# Fri3D_2020_GameOn_00.net
KiCad netlist of a schematic drawn in Altium Designer
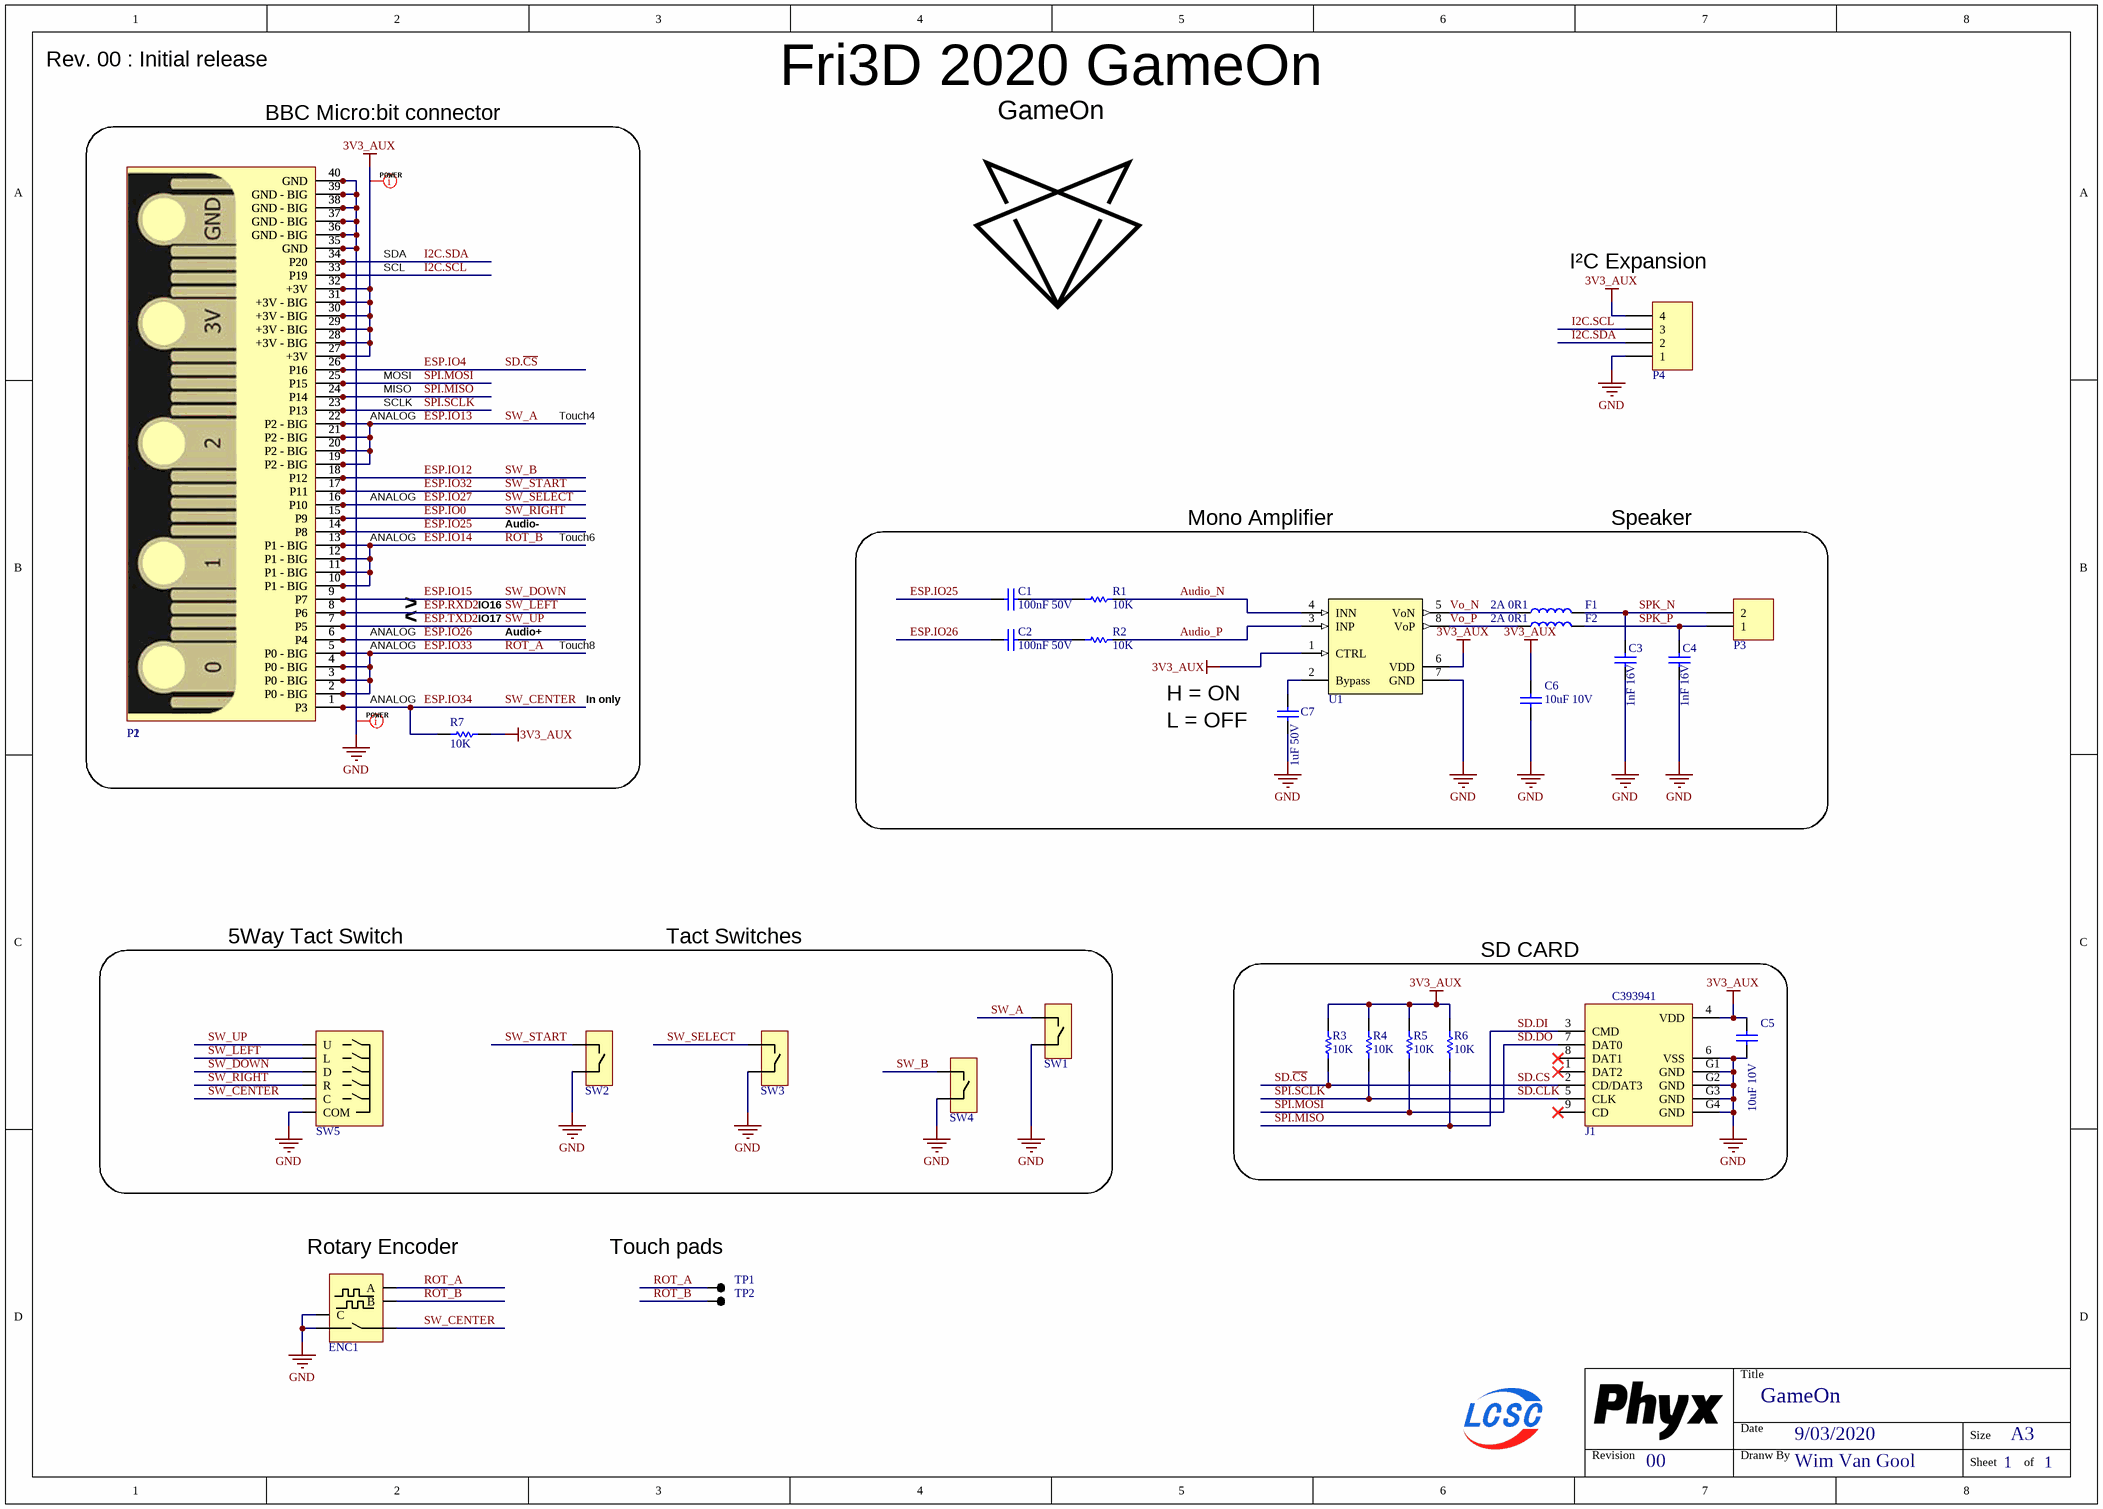
[diagram p0: Fri3D_2020_GameOn_00.SchDoc]

(export (version "E")
  (design (tool "Eeschema 10.0.6"))
  (components
    (comp (ref "C1")
      (value "100nF 50V")
      (footprint "C0603_N")
      (description "Capacitor Ceramic")
      (fields (field (name "Comment") "CAP_CERAMIC"))
      (libsource (lib "Phyx_Components") (part "CAP_CERAMIC"))
    )
    (comp (ref "C2")
      (value "100nF 50V")
      (footprint "C0603_N")
      (description "Capacitor Ceramic")
      (fields (field (name "Comment") "CAP_CERAMIC"))
      (libsource (lib "Phyx_Components") (part "CAP_CERAMIC"))
    )
    (comp (ref "C3")
      (value "1nF 16V")
      (footprint "C0603_N")
      (description "Capacitor Ceramic")
      (fields (field (name "Comment") "CAP_CERAMIC"))
      (libsource (lib "Phyx_Components") (part "CAP_CERAMIC"))
    )
    (comp (ref "C4")
      (value "1nF 16V")
      (footprint "C0603_N")
      (description "Capacitor Ceramic")
      (fields (field (name "Comment") "CAP_CERAMIC"))
      (libsource (lib "Phyx_Components") (part "CAP_CERAMIC"))
    )
    (comp (ref "C5")
      (value "10uF 10V")
      (footprint "C0805_N")
      (description "Capacitor Ceramic")
      (fields (field (name "Comment") "CAP_CERAMIC"))
      (libsource (lib "Phyx_Components") (part "CAP_CERAMIC"))
    )
    (comp (ref "C6")
      (value "10uF 10V")
      (footprint "C0805_N")
      (description "Capacitor Ceramic")
      (fields (field (name "Comment") "CAP_CERAMIC"))
      (libsource (lib "Phyx_Components") (part "CAP_CERAMIC"))
    )
    (comp (ref "C7")
      (value "1uF 50V")
      (footprint "C0603_N")
      (description "Capacitor Ceramic")
      (fields (field (name "Comment") "CAP_CERAMIC"))
      (libsource (lib "Phyx_Components") (part "CAP_CERAMIC"))
    )
    (comp (ref "ENC1")
      (value "Rotary Encoder with Switch")
      (footprint "PEC11-4215F-S0024")
      (libsource (lib "Phyx_Components") (part "ROT_ENC_3P_SW"))
    )
    (comp (ref "F1")
      (value "2A 0R1")
      (footprint "L0805")
      (fields (field (name "Comment") "FERRITE"))
      (libsource (lib "Phyx_Components") (part "FERRITE"))
    )
    (comp (ref "F2")
      (value "2A 0R1")
      (footprint "L0805")
      (fields (field (name "Comment") "FERRITE"))
      (libsource (lib "Phyx_Components") (part "FERRITE"))
    )
    (comp (ref "J1")
      (value "Micro SD PiPo Push-Push")
      (footprint "TFP09-2-12B")
      (description "=Description")
      (fields (field (name "SUPPLIER PART NUMBER 1") "C393941"))
      (libsource (lib "Phyx_Components") (part "TFP09-2-12B"))
    )
    (comp (ref "P1")
      (value "MicroBit 90deg connector Cylconn")
      (footprint "MicroBIT_CYLCONN_SMD_90")
      (libsource (lib "Phyx_Components") (part "Header 40_MicroBit"))
    )
    (comp (ref "P2")
      (value "MicroBit 180deg connector Cylconn")
      (footprint "MicroBIT_CYLCONN_SMD_180")
      (libsource (lib "Phyx_Components") (part "Header 40_MicroBit"))
    )
    (comp (ref "P3")
      (value "Header 2")
      (footprint "HDR1X2")
      (libsource (lib "Phyx_Components") (part "Header 2"))
    )
    (comp (ref "P4")
      (value "Header 4")
      (footprint "HDR1X4")
      (libsource (lib "Phyx_Components") (part "Header 4"))
    )
    (comp (ref "R1")
      (value "10K")
      (footprint "R0603_N")
      (fields (field (name "Comment") "RESISTOR"))
      (libsource (lib "Phyx_Components") (part "RESISTOR"))
    )
    (comp (ref "R2")
      (value "10K")
      (footprint "R0603_N")
      (fields (field (name "Comment") "RESISTOR"))
      (libsource (lib "Phyx_Components") (part "RESISTOR"))
    )
    (comp (ref "R3")
      (value "10K")
      (footprint "R0603_N")
      (fields (field (name "Comment") "RESISTOR"))
      (libsource (lib "Phyx_Components") (part "RESISTOR"))
    )
    (comp (ref "R4")
      (value "10K")
      (footprint "R0603_N")
      (fields (field (name "Comment") "RESISTOR"))
      (libsource (lib "Phyx_Components") (part "RESISTOR"))
    )
    (comp (ref "R5")
      (value "10K")
      (footprint "R0603_N")
      (fields (field (name "Comment") "RESISTOR"))
      (libsource (lib "Phyx_Components") (part "RESISTOR"))
    )
    (comp (ref "R6")
      (value "10K")
      (footprint "R0603_N")
      (fields (field (name "Comment") "RESISTOR"))
      (libsource (lib "Phyx_Components") (part "RESISTOR"))
    )
    (comp (ref "R7")
      (value "10K")
      (footprint "R0603_N")
      (fields (field (name "Comment") "RESISTOR"))
      (libsource (lib "Phyx_Components") (part "RESISTOR"))
    )
    (comp (ref "SW1")
      (value "Default TH TACT")
      (footprint "TACTSW")
      (libsource (lib "Phyx_Components") (part "SW_TACT"))
    )
    (comp (ref "SW2")
      (value "Default TH TACT")
      (footprint "TACTSW")
      (libsource (lib "Phyx_Components") (part "SW_TACT"))
    )
    (comp (ref "SW3")
      (value "Default TH TACT")
      (footprint "TACTSW")
      (libsource (lib "Phyx_Components") (part "SW_TACT"))
    )
    (comp (ref "SW4")
      (value "Default TH TACT")
      (footprint "TACTSW")
      (libsource (lib "Phyx_Components") (part "SW_TACT"))
    )
    (comp (ref "SW5")
      (value "5Way Tact switch")
      (footprint "TACTSW_5W_K1-1506DN-01")
      (libsource (lib "Phyx_Components") (part "SW_TACT_5WAY"))
    )
    (comp (ref "TP1")
      (value "TEST_PAD")
      (footprint "TP_1.2mm")
      (libsource (lib "Phyx_Components") (part "TEST_PAD"))
    )
    (comp (ref "TP2")
      (value "TEST_PAD")
      (footprint "TP_1.2mm")
      (libsource (lib "Phyx_Components") (part "TEST_PAD"))
    )
    (comp (ref "U1")
      (value "5W Class D mono amplifier inducter-less Differential input MSOP8")
      (footprint "MAX_uSOP8")
      (description "=Description")
      (libsource (lib "Phyx_Components") (part "NS4150"))
    )
  )
  (nets
    (net (code "1") (name "/Audio_N") (class "Default")
      (node (ref "R1") (pin "2") (pinfunction "2_2") (pintype "passive"))
      (node (ref "U1") (pin "4") (pinfunction "INN_4") (pintype "input"))
    )
    (net (code "2") (name "/Audio_P") (class "Default")
      (node (ref "R2") (pin "2") (pinfunction "2_2") (pintype "passive"))
      (node (ref "U1") (pin "3") (pinfunction "INP_3") (pintype "input"))
    )
    (net (code "3") (name "/ESP.IO0") (class "Default")
      (node (ref "P1") (pin "15") (pinfunction "P9_15") (pintype "passive"))
      (node (ref "P2") (pin "15") (pinfunction "P9_15") (pintype "passive"))
      (node (ref "SW5") (pin "5") (pinfunction "R_5") (pintype "passive"))
    )
    (net (code "4") (name "/ESP.IO4") (class "Default")
      (node (ref "J1") (pin "2") (pinfunction "CD/DAT3_2") (pintype "passive"))
      (node (ref "P1") (pin "26") (pinfunction "P16_26") (pintype "passive"))
      (node (ref "P2") (pin "26") (pinfunction "P16_26") (pintype "passive"))
      (node (ref "R3") (pin "2") (pinfunction "2_2") (pintype "passive"))
    )
    (net (code "5") (name "/ESP.IO12") (class "Default")
      (node (ref "P1") (pin "18") (pinfunction "P12_18") (pintype "passive"))
      (node (ref "P2") (pin "18") (pinfunction "P12_18") (pintype "passive"))
      (node (ref "SW4") (pin "1") (pinfunction "1_1") (pintype "passive"))
    )
    (net (code "6") (name "/ESP.IO13") (class "Default")
      (node (ref "P1") (pin "19") (pinfunction "P2_-_BIG_19") (pintype "passive"))
      (node (ref "P1") (pin "20") (pinfunction "P2_-_BIG_20") (pintype "passive"))
      (node (ref "P1") (pin "21") (pinfunction "P2_-_BIG_21") (pintype "passive"))
      (node (ref "P1") (pin "22") (pinfunction "P2_-_BIG_22") (pintype "passive"))
      (node (ref "P2") (pin "19") (pinfunction "P2_-_BIG_19") (pintype "passive"))
      (node (ref "P2") (pin "20") (pinfunction "P2_-_BIG_20") (pintype "passive"))
      (node (ref "P2") (pin "21") (pinfunction "P2_-_BIG_21") (pintype "passive"))
      (node (ref "P2") (pin "22") (pinfunction "P2_-_BIG_22") (pintype "passive"))
      (node (ref "SW1") (pin "1") (pinfunction "1_1") (pintype "passive"))
    )
    (net (code "7") (name "/ESP.IO14") (class "Default")
      (node (ref "ENC1") (pin "B") (pinfunction "B_B") (pintype "passive"))
      (node (ref "P1") (pin "10") (pinfunction "P1_-_BIG_10") (pintype "passive"))
      (node (ref "P1") (pin "11") (pinfunction "P1_-_BIG_11") (pintype "passive"))
      (node (ref "P1") (pin "12") (pinfunction "P1_-_BIG_12") (pintype "passive"))
      (node (ref "P1") (pin "13") (pinfunction "P1_-_BIG_13") (pintype "passive"))
      (node (ref "P2") (pin "10") (pinfunction "P1_-_BIG_10") (pintype "passive"))
      (node (ref "P2") (pin "11") (pinfunction "P1_-_BIG_11") (pintype "passive"))
      (node (ref "P2") (pin "12") (pinfunction "P1_-_BIG_12") (pintype "passive"))
      (node (ref "P2") (pin "13") (pinfunction "P1_-_BIG_13") (pintype "passive"))
      (node (ref "TP2") (pin "1") (pinfunction "1_1") (pintype "passive"))
    )
    (net (code "8") (name "/ESP.IO15") (class "Default")
      (node (ref "P1") (pin "9") (pinfunction "P7_9") (pintype "passive"))
      (node (ref "P2") (pin "9") (pinfunction "P7_9") (pintype "passive"))
      (node (ref "SW5") (pin "3") (pinfunction "D_3") (pintype "passive"))
    )
    (net (code "9") (name "/ESP.IO25") (class "Default")
      (node (ref "C1") (pin "2") (pinfunction "2_2") (pintype "passive"))
      (node (ref "P1") (pin "14") (pinfunction "P8_14") (pintype "passive"))
      (node (ref "P2") (pin "14") (pinfunction "P8_14") (pintype "passive"))
    )
    (net (code "10") (name "/ESP.IO26") (class "Default")
      (node (ref "C2") (pin "2") (pinfunction "2_2") (pintype "passive"))
      (node (ref "P1") (pin "6") (pinfunction "P4_6") (pintype "passive"))
      (node (ref "P2") (pin "6") (pinfunction "P4_6") (pintype "passive"))
    )
    (net (code "11") (name "/ESP.IO27") (class "Default")
      (node (ref "P1") (pin "16") (pinfunction "P10_16") (pintype "passive"))
      (node (ref "P2") (pin "16") (pinfunction "P10_16") (pintype "passive"))
      (node (ref "SW3") (pin "1") (pinfunction "1_1") (pintype "passive"))
    )
    (net (code "12") (name "/ESP.IO32") (class "Default")
      (node (ref "P1") (pin "17") (pinfunction "P11_17") (pintype "passive"))
      (node (ref "P2") (pin "17") (pinfunction "P11_17") (pintype "passive"))
      (node (ref "SW2") (pin "1") (pinfunction "1_1") (pintype "passive"))
    )
    (net (code "13") (name "/ESP.IO33") (class "Default")
      (node (ref "ENC1") (pin "A") (pinfunction "A_A") (pintype "passive"))
      (node (ref "P1") (pin "2") (pinfunction "P0_-_BIG_2") (pintype "passive"))
      (node (ref "P1") (pin "3") (pinfunction "P0_-_BIG_3") (pintype "passive"))
      (node (ref "P1") (pin "4") (pinfunction "P0_-_BIG_4") (pintype "passive"))
      (node (ref "P1") (pin "5") (pinfunction "P0_-_BIG_5") (pintype "passive"))
      (node (ref "P2") (pin "2") (pinfunction "P0_-_BIG_2") (pintype "passive"))
      (node (ref "P2") (pin "3") (pinfunction "P0_-_BIG_3") (pintype "passive"))
      (node (ref "P2") (pin "4") (pinfunction "P0_-_BIG_4") (pintype "passive"))
      (node (ref "P2") (pin "5") (pinfunction "P0_-_BIG_5") (pintype "passive"))
      (node (ref "TP1") (pin "1") (pinfunction "1_1") (pintype "passive"))
    )
    (net (code "14") (name "/ESP.IO34") (class "Default")
      (node (ref "ENC1") (pin "2") (pinfunction "2_2") (pintype "passive"))
      (node (ref "P1") (pin "1") (pinfunction "P3_1") (pintype "passive"))
      (node (ref "P2") (pin "1") (pinfunction "P3_1") (pintype "passive"))
      (node (ref "R7") (pin "2") (pinfunction "2_2") (pintype "passive"))
      (node (ref "SW5") (pin "6") (pinfunction "C_6") (pintype "passive"))
    )
    (net (code "15") (name "/ESP.RXD2") (class "Default")
      (node (ref "P1") (pin "8") (pinfunction "P6_8") (pintype "passive"))
      (node (ref "P2") (pin "8") (pinfunction "P6_8") (pintype "passive"))
      (node (ref "SW5") (pin "2") (pinfunction "L_2") (pintype "passive"))
    )
    (net (code "16") (name "/ESP.TXD2") (class "Default")
      (node (ref "P1") (pin "7") (pinfunction "P5_7") (pintype "passive"))
      (node (ref "P2") (pin "7") (pinfunction "P5_7") (pintype "passive"))
      (node (ref "SW5") (pin "1") (pinfunction "U_1") (pintype "passive"))
    )
    (net (code "17") (name "/I2C.SCL") (class "Default")
      (node (ref "P1") (pin "33") (pinfunction "P19_33") (pintype "passive"))
      (node (ref "P2") (pin "33") (pinfunction "P19_33") (pintype "passive"))
      (node (ref "P4") (pin "3") (pinfunction "3_3") (pintype "passive"))
    )
    (net (code "18") (name "/I2C.SDA") (class "Default")
      (node (ref "P1") (pin "34") (pinfunction "P20_34") (pintype "passive"))
      (node (ref "P2") (pin "34") (pinfunction "P20_34") (pintype "passive"))
      (node (ref "P4") (pin "2") (pinfunction "2_2") (pintype "passive"))
    )
    (net (code "19") (name "/SD.CLK") (class "Default")
      (node (ref "J1") (pin "5") (pinfunction "CLK_5") (pintype "passive"))
      (node (ref "P1") (pin "23") (pinfunction "P13_23") (pintype "passive"))
      (node (ref "P2") (pin "23") (pinfunction "P13_23") (pintype "passive"))
      (node (ref "R4") (pin "2") (pinfunction "2_2") (pintype "passive"))
    )
    (net (code "20") (name "/SD.DI") (class "Default")
      (node (ref "J1") (pin "3") (pinfunction "CMD_3") (pintype "passive"))
      (node (ref "P1") (pin "24") (pinfunction "P14_24") (pintype "passive"))
      (node (ref "P2") (pin "24") (pinfunction "P14_24") (pintype "passive"))
      (node (ref "R6") (pin "2") (pinfunction "2_2") (pintype "passive"))
    )
    (net (code "21") (name "/SD.DO") (class "Default")
      (node (ref "J1") (pin "7") (pinfunction "DAT0_7") (pintype "passive"))
      (node (ref "P1") (pin "25") (pinfunction "P15_25") (pintype "passive"))
      (node (ref "P2") (pin "25") (pinfunction "P15_25") (pintype "passive"))
      (node (ref "R5") (pin "2") (pinfunction "2_2") (pintype "passive"))
    )
    (net (code "22") (name "/SPK_N") (class "Default")
      (node (ref "C3") (pin "1") (pinfunction "1_1") (pintype "passive"))
      (node (ref "F1") (pin "2") (pinfunction "2_2") (pintype "passive"))
      (node (ref "P3") (pin "2") (pinfunction "2_2") (pintype "passive"))
    )
    (net (code "23") (name "/SPK_P") (class "Default")
      (node (ref "C4") (pin "1") (pinfunction "1_1") (pintype "passive"))
      (node (ref "F2") (pin "2") (pinfunction "2_2") (pintype "passive"))
      (node (ref "P3") (pin "1") (pinfunction "1_1") (pintype "passive"))
    )
    (net (code "24") (name "/Vo_N") (class "Default")
      (node (ref "F1") (pin "1") (pinfunction "1_1") (pintype "passive"))
      (node (ref "U1") (pin "5") (pinfunction "VoN_5") (pintype "output"))
    )
    (net (code "25") (name "/Vo_P") (class "Default")
      (node (ref "F2") (pin "1") (pinfunction "1_1") (pintype "passive"))
      (node (ref "U1") (pin "8") (pinfunction "VoP_8") (pintype "output"))
    )
    (net (code "26") (name "3V3_AUX") (class "Default")
      (node (ref "C5") (pin "1") (pinfunction "1_1") (pintype "passive"))
      (node (ref "C6") (pin "1") (pinfunction "1_1") (pintype "passive"))
      (node (ref "J1") (pin "4") (pinfunction "VDD_4") (pintype "power_in"))
      (node (ref "P1") (pin "27") (pinfunction "+3V_27") (pintype "passive"))
      (node (ref "P1") (pin "28") (pinfunction "+3V_-_BIG_28") (pintype "passive"))
      (node (ref "P1") (pin "29") (pinfunction "+3V_-_BIG_29") (pintype "passive"))
      (node (ref "P1") (pin "30") (pinfunction "+3V_-_BIG_30") (pintype "passive"))
      (node (ref "P1") (pin "31") (pinfunction "+3V_-_BIG_31") (pintype "passive"))
      (node (ref "P1") (pin "32") (pinfunction "+3V_32") (pintype "passive"))
      (node (ref "P2") (pin "27") (pinfunction "+3V_27") (pintype "passive"))
      (node (ref "P2") (pin "28") (pinfunction "+3V_-_BIG_28") (pintype "passive"))
      (node (ref "P2") (pin "29") (pinfunction "+3V_-_BIG_29") (pintype "passive"))
      (node (ref "P2") (pin "30") (pinfunction "+3V_-_BIG_30") (pintype "passive"))
      (node (ref "P2") (pin "31") (pinfunction "+3V_-_BIG_31") (pintype "passive"))
      (node (ref "P2") (pin "32") (pinfunction "+3V_32") (pintype "passive"))
      (node (ref "P4") (pin "4") (pinfunction "4_4") (pintype "passive"))
      (node (ref "R3") (pin "1") (pinfunction "1_1") (pintype "passive"))
      (node (ref "R4") (pin "1") (pinfunction "1_1") (pintype "passive"))
      (node (ref "R5") (pin "1") (pinfunction "1_1") (pintype "passive"))
      (node (ref "R6") (pin "1") (pinfunction "1_1") (pintype "passive"))
      (node (ref "R7") (pin "1") (pinfunction "1_1") (pintype "passive"))
      (node (ref "U1") (pin "1") (pinfunction "CTRL_1") (pintype "input"))
      (node (ref "U1") (pin "6") (pinfunction "VDD_6") (pintype "power_in"))
    )
    (net (code "27") (name "GND") (class "Default")
      (node (ref "C3") (pin "2") (pinfunction "2_2") (pintype "passive"))
      (node (ref "C4") (pin "2") (pinfunction "2_2") (pintype "passive"))
      (node (ref "C5") (pin "2") (pinfunction "2_2") (pintype "passive"))
      (node (ref "C6") (pin "2") (pinfunction "2_2") (pintype "passive"))
      (node (ref "C7") (pin "2") (pinfunction "2_2") (pintype "passive"))
      (node (ref "ENC1") (pin "1") (pinfunction "1_1") (pintype "passive"))
      (node (ref "ENC1") (pin "C") (pinfunction "C_C") (pintype "passive"))
      (node (ref "J1") (pin "6") (pinfunction "VSS_6") (pintype "power_in"))
      (node (ref "J1") (pin "G1") (pinfunction "GND_G1") (pintype "power_in"))
      (node (ref "J1") (pin "G2") (pinfunction "GND_G2") (pintype "power_in"))
      (node (ref "J1") (pin "G3") (pinfunction "GND_G3") (pintype "power_in"))
      (node (ref "J1") (pin "G4") (pinfunction "GND_G4") (pintype "power_in"))
      (node (ref "P1") (pin "35") (pinfunction "GND_35") (pintype "passive"))
      (node (ref "P1") (pin "36") (pinfunction "GND_-_BIG_36") (pintype "passive"))
      (node (ref "P1") (pin "37") (pinfunction "GND_-_BIG_37") (pintype "passive"))
      (node (ref "P1") (pin "38") (pinfunction "GND_-_BIG_38") (pintype "passive"))
      (node (ref "P1") (pin "39") (pinfunction "GND_-_BIG_39") (pintype "passive"))
      (node (ref "P1") (pin "40") (pinfunction "GND_40") (pintype "passive"))
      (node (ref "P2") (pin "35") (pinfunction "GND_35") (pintype "passive"))
      (node (ref "P2") (pin "36") (pinfunction "GND_-_BIG_36") (pintype "passive"))
      (node (ref "P2") (pin "37") (pinfunction "GND_-_BIG_37") (pintype "passive"))
      (node (ref "P2") (pin "38") (pinfunction "GND_-_BIG_38") (pintype "passive"))
      (node (ref "P2") (pin "39") (pinfunction "GND_-_BIG_39") (pintype "passive"))
      (node (ref "P2") (pin "40") (pinfunction "GND_40") (pintype "passive"))
      (node (ref "P4") (pin "1") (pinfunction "1_1") (pintype "passive"))
      (node (ref "SW1") (pin "2") (pinfunction "2_2") (pintype "passive"))
      (node (ref "SW2") (pin "2") (pinfunction "2_2") (pintype "passive"))
      (node (ref "SW3") (pin "2") (pinfunction "2_2") (pintype "passive"))
      (node (ref "SW4") (pin "2") (pinfunction "2_2") (pintype "passive"))
      (node (ref "SW5") (pin "4") (pinfunction "COM_4") (pintype "passive"))
      (node (ref "U1") (pin "7") (pinfunction "GND_7") (pintype "power_in"))
    )
    (net (code "28") (name "Net-(C1-Pad1)") (class "Default")
      (node (ref "C1") (pin "1") (pinfunction "1_1") (pintype "passive"))
      (node (ref "R1") (pin "1") (pinfunction "1_1") (pintype "passive"))
    )
    (net (code "29") (name "Net-(C2-Pad1)") (class "Default")
      (node (ref "C2") (pin "1") (pinfunction "1_1") (pintype "passive"))
      (node (ref "R2") (pin "1") (pinfunction "1_1") (pintype "passive"))
    )
    (net (code "30") (name "Net-(U1-Bypass)") (class "Default")
      (node (ref "C7") (pin "1") (pinfunction "1_1") (pintype "passive"))
      (node (ref "U1") (pin "2") (pinfunction "Bypass_2") (pintype "passive"))
    )
    (net (code "31") (name "unconnected-(J1-CD-Pad9)") (class "Default")
      (node (ref "J1") (pin "9") (pinfunction "CD_9") (pintype "passive+no_connect"))
    )
    (net (code "32") (name "unconnected-(J1-DAT1-Pad8)") (class "Default")
      (node (ref "J1") (pin "8") (pinfunction "DAT1_8") (pintype "passive+no_connect"))
    )
    (net (code "33") (name "unconnected-(J1-DAT2-Pad1)") (class "Default")
      (node (ref "J1") (pin "1") (pinfunction "DAT2_1") (pintype "passive+no_connect"))
    )
  )
)
